# Tacho_Update_Platine_mehrfach.net
KiCad netlist of a schematic drawn in EAGLE
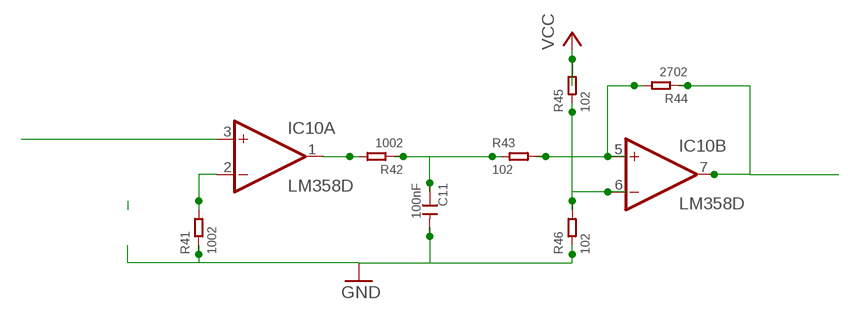
[diagram p0: schematic, sheet 1]
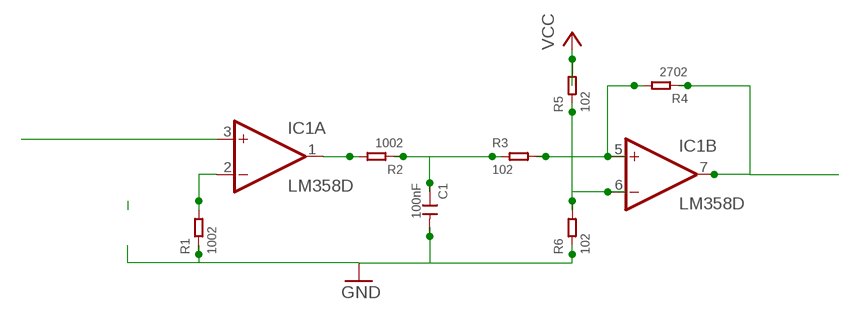
[diagram p1: schematic, sheet 2]
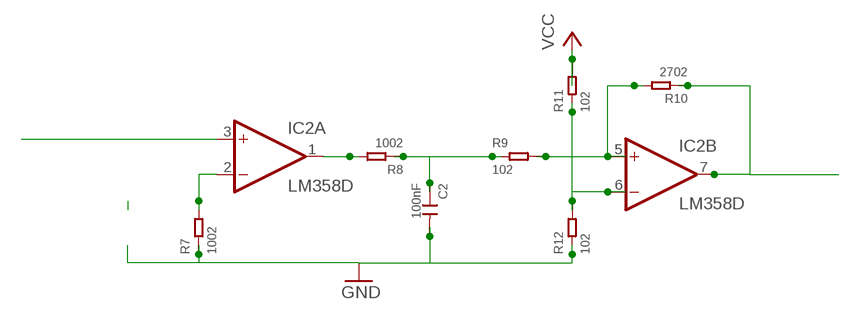
[diagram p2: schematic, sheet 3]
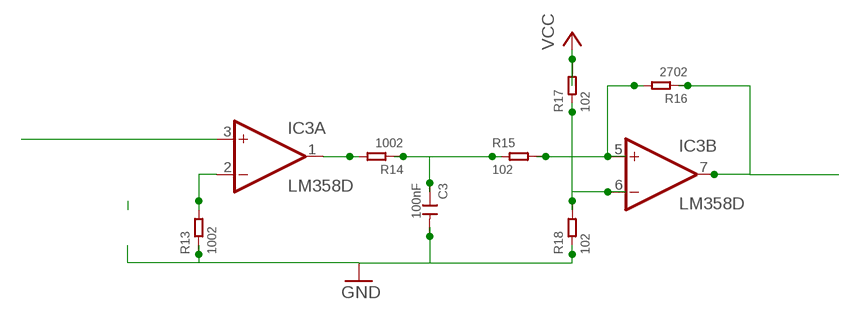
[diagram p3: schematic, sheet 4]
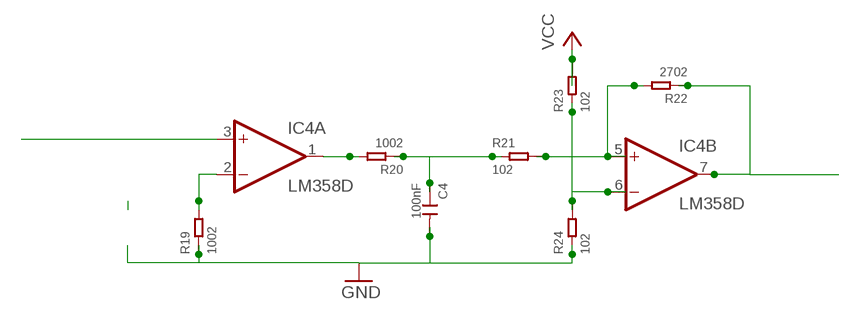
[diagram p4: schematic, sheet 5]
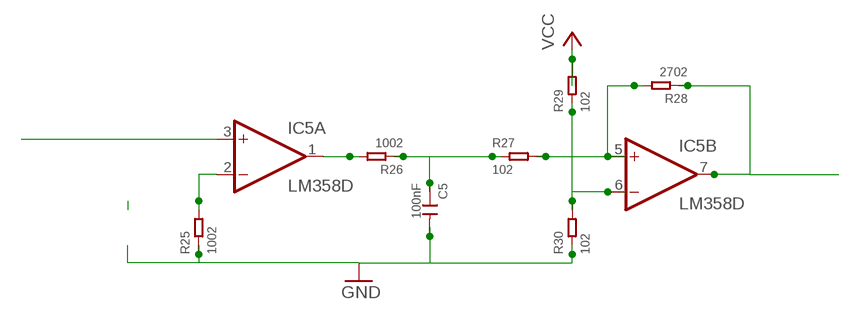
[diagram p5: schematic, sheet 6]
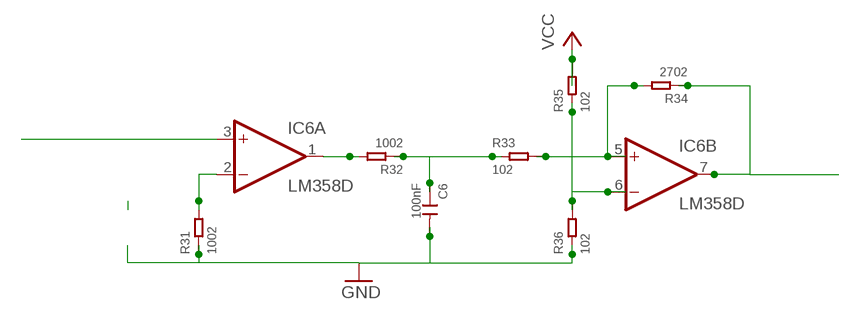
[diagram p6: schematic, sheet 7]
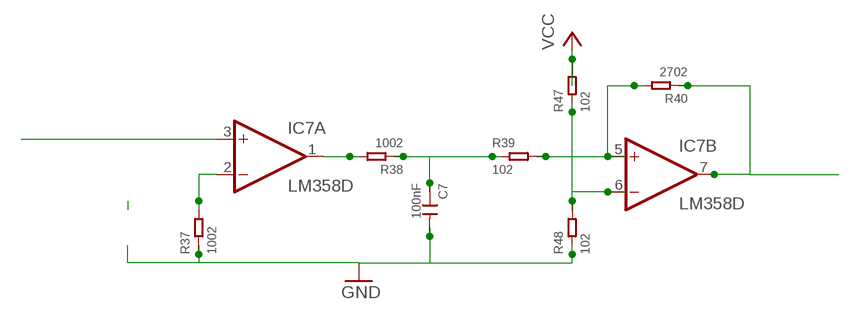
[diagram p7: schematic, sheet 8]
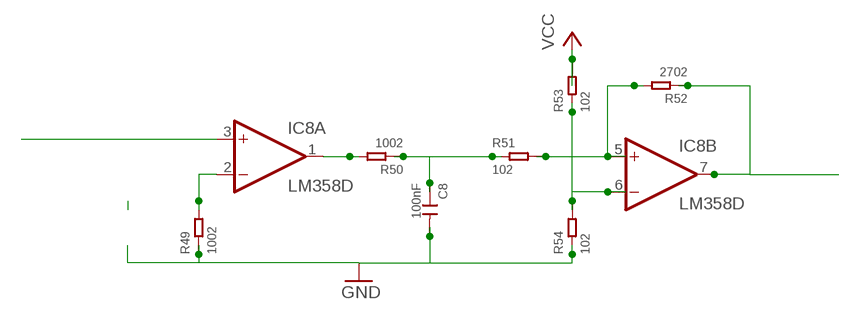
[diagram p8: schematic, sheet 9]
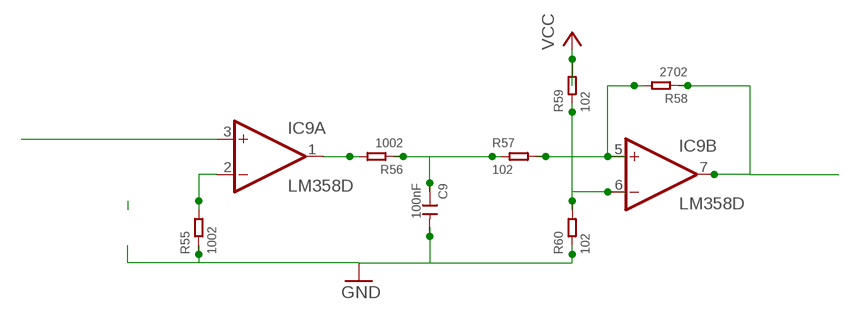
[diagram p9: schematic, sheet 10]
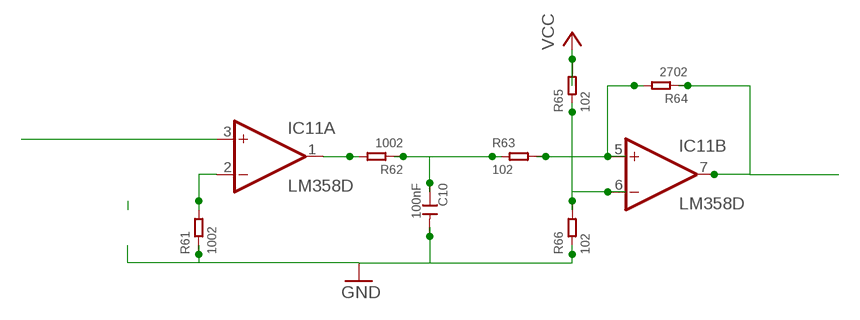
[diagram p10: schematic, sheet 11]
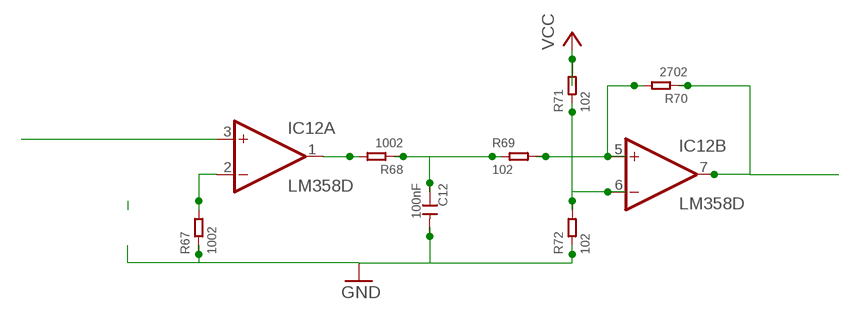
[diagram p11: schematic, sheet 12]
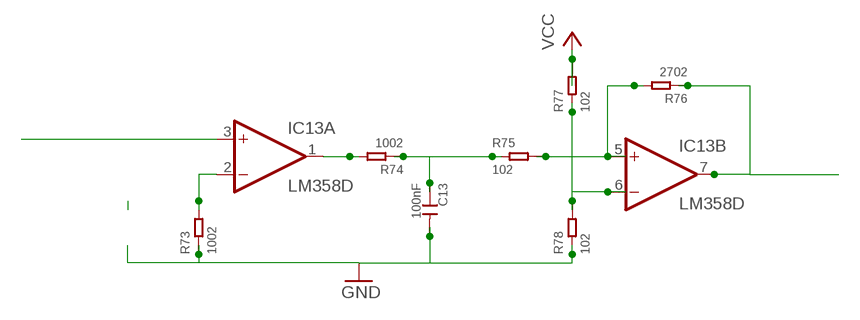
[diagram p12: schematic, sheet 13]
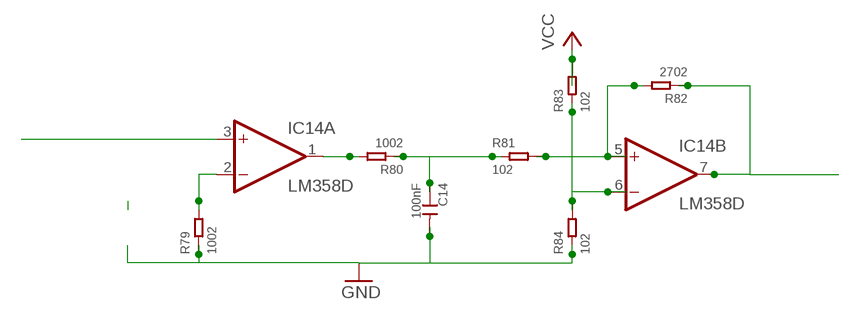
[diagram p13: schematic, sheet 14]
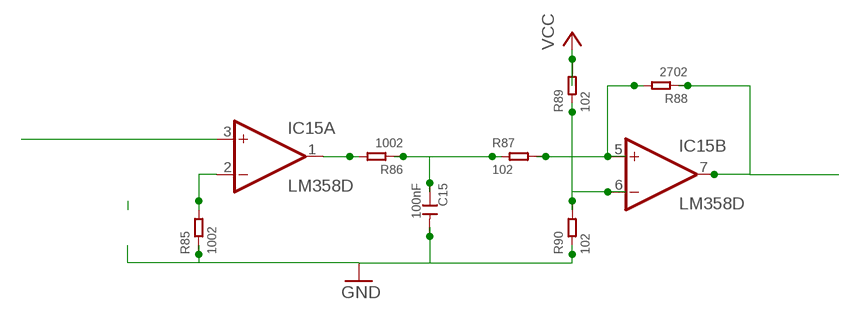
[diagram p14: schematic, sheet 15]
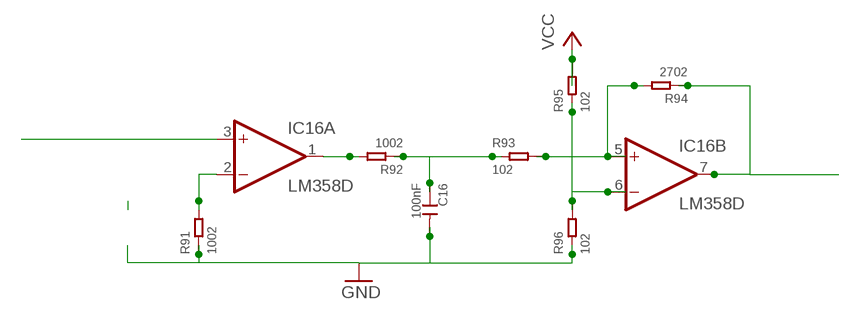
[diagram p15: schematic, sheet 16]

(export (version "E")
  (design (tool "Eeschema 10.0.6"))
  (components
    (comp (ref "C10")
      (value "100nF")
      (footprint "eagle-import:C0805")
      (fields (field (name "MPN") "CC0805KRX7R9BB104"))
      (libsource (lib "eagle-import") (part "CERAMIC-100NF-50V-10%-X7R(0805)"))
    )
    (comp (ref "IC11")
      (value "LM358D")
      (footprint "eagle-import:SO08")
      (libsource (lib "eagle-import") (part "LM358D"))
    )
    (comp (ref "R61")
      (value "1002")
      (footprint "eagle-import:R0805")
      (fields (field (name "MPN") "RC0805FR-0710KL"))
      (libsource (lib "eagle-import") (part "SMD-RES-10K-1%-1/8W(0805)"))
    )
    (comp (ref "R62")
      (value "1002")
      (footprint "eagle-import:R0805")
      (fields (field (name "MPN") "RC0805FR-0710KL"))
      (libsource (lib "eagle-import") (part "SMD-RES-10K-1%-1/8W(0805)"))
    )
    (comp (ref "R63")
      (value "102")
      (footprint "eagle-import:R0805")
      (fields (field (name "MPN") "RC0805JR-071KL"))
      (libsource (lib "eagle-import") (part "SMD-RES-1K-5%-1/8W(0805)"))
    )
    (comp (ref "R64")
      (value "2702")
      (footprint "eagle-import:R0805")
      (fields (field (name "MPN") "RC0805JR-074K7L"))
      (libsource (lib "eagle-import") (part "SMD-RES-4.7K-5%-1/8W(0805)"))
    )
    (comp (ref "R65")
      (value "102")
      (footprint "eagle-import:R0805")
      (fields (field (name "MPN") "RC0805JR-071KL"))
      (libsource (lib "eagle-import") (part "SMD-RES-1K-5%-1/8W(0805)"))
    )
    (comp (ref "R66")
      (value "102")
      (footprint "eagle-import:R0805")
      (fields (field (name "MPN") "RC0805JR-071KL"))
      (libsource (lib "eagle-import") (part "SMD-RES-1K-5%-1/8W(0805)"))
    )
    (comp (ref "C15")
      (value "100nF")
      (footprint "eagle-import:C0805")
      (fields (field (name "MPN") "CC0805KRX7R9BB104"))
      (libsource (lib "eagle-import") (part "CERAMIC-100NF-50V-10%-X7R(0805)"))
    )
    (comp (ref "IC15")
      (value "LM358D")
      (footprint "eagle-import:SO08")
      (libsource (lib "eagle-import") (part "LM358D"))
    )
    (comp (ref "R85")
      (value "1002")
      (footprint "eagle-import:R0805")
      (fields (field (name "MPN") "RC0805FR-0710KL"))
      (libsource (lib "eagle-import") (part "SMD-RES-10K-1%-1/8W(0805)"))
    )
    (comp (ref "R86")
      (value "1002")
      (footprint "eagle-import:R0805")
      (fields (field (name "MPN") "RC0805FR-0710KL"))
      (libsource (lib "eagle-import") (part "SMD-RES-10K-1%-1/8W(0805)"))
    )
    (comp (ref "R87")
      (value "102")
      (footprint "eagle-import:R0805")
      (fields (field (name "MPN") "RC0805JR-071KL"))
      (libsource (lib "eagle-import") (part "SMD-RES-1K-5%-1/8W(0805)"))
    )
    (comp (ref "R88")
      (value "2702")
      (footprint "eagle-import:R0805")
      (fields (field (name "MPN") "RC0805JR-074K7L"))
      (libsource (lib "eagle-import") (part "SMD-RES-4.7K-5%-1/8W(0805)"))
    )
    (comp (ref "R89")
      (value "102")
      (footprint "eagle-import:R0805")
      (fields (field (name "MPN") "RC0805JR-071KL"))
      (libsource (lib "eagle-import") (part "SMD-RES-1K-5%-1/8W(0805)"))
    )
    (comp (ref "R90")
      (value "102")
      (footprint "eagle-import:R0805")
      (fields (field (name "MPN") "RC0805JR-071KL"))
      (libsource (lib "eagle-import") (part "SMD-RES-1K-5%-1/8W(0805)"))
    )
    (comp (ref "C4")
      (value "100nF")
      (footprint "eagle-import:C0805")
      (fields (field (name "MPN") "CC0805KRX7R9BB104"))
      (libsource (lib "eagle-import") (part "CERAMIC-100NF-50V-10%-X7R(0805)"))
    )
    (comp (ref "IC4")
      (value "LM358D")
      (footprint "eagle-import:SO08")
      (libsource (lib "eagle-import") (part "LM358D"))
    )
    (comp (ref "R19")
      (value "1002")
      (footprint "eagle-import:R0805")
      (fields (field (name "MPN") "RC0805FR-0710KL"))
      (libsource (lib "eagle-import") (part "SMD-RES-10K-1%-1/8W(0805)"))
    )
    (comp (ref "R20")
      (value "1002")
      (footprint "eagle-import:R0805")
      (fields (field (name "MPN") "RC0805FR-0710KL"))
      (libsource (lib "eagle-import") (part "SMD-RES-10K-1%-1/8W(0805)"))
    )
    (comp (ref "R21")
      (value "102")
      (footprint "eagle-import:R0805")
      (fields (field (name "MPN") "RC0805JR-071KL"))
      (libsource (lib "eagle-import") (part "SMD-RES-1K-5%-1/8W(0805)"))
    )
    (comp (ref "R22")
      (value "2702")
      (footprint "eagle-import:R0805")
      (fields (field (name "MPN") "RC0805JR-074K7L"))
      (libsource (lib "eagle-import") (part "SMD-RES-4.7K-5%-1/8W(0805)"))
    )
    (comp (ref "R23")
      (value "102")
      (footprint "eagle-import:R0805")
      (fields (field (name "MPN") "RC0805JR-071KL"))
      (libsource (lib "eagle-import") (part "SMD-RES-1K-5%-1/8W(0805)"))
    )
    (comp (ref "R24")
      (value "102")
      (footprint "eagle-import:R0805")
      (fields (field (name "MPN") "RC0805JR-071KL"))
      (libsource (lib "eagle-import") (part "SMD-RES-1K-5%-1/8W(0805)"))
    )
    (comp (ref "C12")
      (value "100nF")
      (footprint "eagle-import:C0805")
      (fields (field (name "MPN") "CC0805KRX7R9BB104"))
      (libsource (lib "eagle-import") (part "CERAMIC-100NF-50V-10%-X7R(0805)"))
    )
    (comp (ref "IC12")
      (value "LM358D")
      (footprint "eagle-import:SO08")
      (libsource (lib "eagle-import") (part "LM358D"))
    )
    (comp (ref "R67")
      (value "1002")
      (footprint "eagle-import:R0805")
      (fields (field (name "MPN") "RC0805FR-0710KL"))
      (libsource (lib "eagle-import") (part "SMD-RES-10K-1%-1/8W(0805)"))
    )
    (comp (ref "R68")
      (value "1002")
      (footprint "eagle-import:R0805")
      (fields (field (name "MPN") "RC0805FR-0710KL"))
      (libsource (lib "eagle-import") (part "SMD-RES-10K-1%-1/8W(0805)"))
    )
    (comp (ref "R69")
      (value "102")
      (footprint "eagle-import:R0805")
      (fields (field (name "MPN") "RC0805JR-071KL"))
      (libsource (lib "eagle-import") (part "SMD-RES-1K-5%-1/8W(0805)"))
    )
    (comp (ref "R70")
      (value "2702")
      (footprint "eagle-import:R0805")
      (fields (field (name "MPN") "RC0805JR-074K7L"))
      (libsource (lib "eagle-import") (part "SMD-RES-4.7K-5%-1/8W(0805)"))
    )
    (comp (ref "R71")
      (value "102")
      (footprint "eagle-import:R0805")
      (fields (field (name "MPN") "RC0805JR-071KL"))
      (libsource (lib "eagle-import") (part "SMD-RES-1K-5%-1/8W(0805)"))
    )
    (comp (ref "R72")
      (value "102")
      (footprint "eagle-import:R0805")
      (fields (field (name "MPN") "RC0805JR-071KL"))
      (libsource (lib "eagle-import") (part "SMD-RES-1K-5%-1/8W(0805)"))
    )
    (comp (ref "C1")
      (value "100nF")
      (footprint "eagle-import:C0805")
      (fields (field (name "MPN") "CC0805KRX7R9BB104"))
      (libsource (lib "eagle-import") (part "CERAMIC-100NF-50V-10%-X7R(0805)"))
    )
    (comp (ref "IC1")
      (value "LM358D")
      (footprint "eagle-import:SO08")
      (libsource (lib "eagle-import") (part "LM358D"))
    )
    (comp (ref "R1")
      (value "1002")
      (footprint "eagle-import:R0805")
      (fields (field (name "MPN") "RC0805FR-0710KL"))
      (libsource (lib "eagle-import") (part "SMD-RES-10K-1%-1/8W(0805)"))
    )
    (comp (ref "R2")
      (value "1002")
      (footprint "eagle-import:R0805")
      (fields (field (name "MPN") "RC0805FR-0710KL"))
      (libsource (lib "eagle-import") (part "SMD-RES-10K-1%-1/8W(0805)"))
    )
    (comp (ref "R3")
      (value "102")
      (footprint "eagle-import:R0805")
      (fields (field (name "MPN") "RC0805JR-071KL"))
      (libsource (lib "eagle-import") (part "SMD-RES-1K-5%-1/8W(0805)"))
    )
    (comp (ref "R4")
      (value "2702")
      (footprint "eagle-import:R0805")
      (fields (field (name "MPN") "RC0805JR-074K7L"))
      (libsource (lib "eagle-import") (part "SMD-RES-4.7K-5%-1/8W(0805)"))
    )
    (comp (ref "R5")
      (value "102")
      (footprint "eagle-import:R0805")
      (fields (field (name "MPN") "RC0805JR-071KL"))
      (libsource (lib "eagle-import") (part "SMD-RES-1K-5%-1/8W(0805)"))
    )
    (comp (ref "R6")
      (value "102")
      (footprint "eagle-import:R0805")
      (fields (field (name "MPN") "RC0805JR-071KL"))
      (libsource (lib "eagle-import") (part "SMD-RES-1K-5%-1/8W(0805)"))
    )
    (comp (ref "C2")
      (value "100nF")
      (footprint "eagle-import:C0805")
      (fields (field (name "MPN") "CC0805KRX7R9BB104"))
      (libsource (lib "eagle-import") (part "CERAMIC-100NF-50V-10%-X7R(0805)"))
    )
    (comp (ref "IC2")
      (value "LM358D")
      (footprint "eagle-import:SO08")
      (libsource (lib "eagle-import") (part "LM358D"))
    )
    (comp (ref "R7")
      (value "1002")
      (footprint "eagle-import:R0805")
      (fields (field (name "MPN") "RC0805FR-0710KL"))
      (libsource (lib "eagle-import") (part "SMD-RES-10K-1%-1/8W(0805)"))
    )
    (comp (ref "R8")
      (value "1002")
      (footprint "eagle-import:R0805")
      (fields (field (name "MPN") "RC0805FR-0710KL"))
      (libsource (lib "eagle-import") (part "SMD-RES-10K-1%-1/8W(0805)"))
    )
    (comp (ref "R9")
      (value "102")
      (footprint "eagle-import:R0805")
      (fields (field (name "MPN") "RC0805JR-071KL"))
      (libsource (lib "eagle-import") (part "SMD-RES-1K-5%-1/8W(0805)"))
    )
    (comp (ref "R10")
      (value "2702")
      (footprint "eagle-import:R0805")
      (fields (field (name "MPN") "RC0805JR-074K7L"))
      (libsource (lib "eagle-import") (part "SMD-RES-4.7K-5%-1/8W(0805)"))
    )
    (comp (ref "R11")
      (value "102")
      (footprint "eagle-import:R0805")
      (fields (field (name "MPN") "RC0805JR-071KL"))
      (libsource (lib "eagle-import") (part "SMD-RES-1K-5%-1/8W(0805)"))
    )
    (comp (ref "R12")
      (value "102")
      (footprint "eagle-import:R0805")
      (fields (field (name "MPN") "RC0805JR-071KL"))
      (libsource (lib "eagle-import") (part "SMD-RES-1K-5%-1/8W(0805)"))
    )
    (comp (ref "C11")
      (value "100nF")
      (footprint "eagle-import:C0805")
      (fields (field (name "MPN") "CC0805KRX7R9BB104"))
      (libsource (lib "eagle-import") (part "CERAMIC-100NF-50V-10%-X7R(0805)"))
    )
    (comp (ref "IC10")
      (value "LM358D")
      (footprint "eagle-import:SO08")
      (libsource (lib "eagle-import") (part "LM358D"))
    )
    (comp (ref "R41")
      (value "1002")
      (footprint "eagle-import:R0805")
      (fields (field (name "MPN") "RC0805FR-0710KL"))
      (libsource (lib "eagle-import") (part "SMD-RES-10K-1%-1/8W(0805)"))
    )
    (comp (ref "R42")
      (value "1002")
      (footprint "eagle-import:R0805")
      (fields (field (name "MPN") "RC0805FR-0710KL"))
      (libsource (lib "eagle-import") (part "SMD-RES-10K-1%-1/8W(0805)"))
    )
    (comp (ref "R43")
      (value "102")
      (footprint "eagle-import:R0805")
      (fields (field (name "MPN") "RC0805JR-071KL"))
      (libsource (lib "eagle-import") (part "SMD-RES-1K-5%-1/8W(0805)"))
    )
    (comp (ref "R44")
      (value "2702")
      (footprint "eagle-import:R0805")
      (fields (field (name "MPN") "RC0805JR-074K7L"))
      (libsource (lib "eagle-import") (part "SMD-RES-4.7K-5%-1/8W(0805)"))
    )
    (comp (ref "R45")
      (value "102")
      (footprint "eagle-import:R0805")
      (fields (field (name "MPN") "RC0805JR-071KL"))
      (libsource (lib "eagle-import") (part "SMD-RES-1K-5%-1/8W(0805)"))
    )
    (comp (ref "R46")
      (value "102")
      (footprint "eagle-import:R0805")
      (fields (field (name "MPN") "RC0805JR-071KL"))
      (libsource (lib "eagle-import") (part "SMD-RES-1K-5%-1/8W(0805)"))
    )
    (comp (ref "C13")
      (value "100nF")
      (footprint "eagle-import:C0805")
      (fields (field (name "MPN") "CC0805KRX7R9BB104"))
      (libsource (lib "eagle-import") (part "CERAMIC-100NF-50V-10%-X7R(0805)"))
    )
    (comp (ref "IC13")
      (value "LM358D")
      (footprint "eagle-import:SO08")
      (libsource (lib "eagle-import") (part "LM358D"))
    )
    (comp (ref "R73")
      (value "1002")
      (footprint "eagle-import:R0805")
      (fields (field (name "MPN") "RC0805FR-0710KL"))
      (libsource (lib "eagle-import") (part "SMD-RES-10K-1%-1/8W(0805)"))
    )
    (comp (ref "R74")
      (value "1002")
      (footprint "eagle-import:R0805")
      (fields (field (name "MPN") "RC0805FR-0710KL"))
      (libsource (lib "eagle-import") (part "SMD-RES-10K-1%-1/8W(0805)"))
    )
    (comp (ref "R75")
      (value "102")
      (footprint "eagle-import:R0805")
      (fields (field (name "MPN") "RC0805JR-071KL"))
      (libsource (lib "eagle-import") (part "SMD-RES-1K-5%-1/8W(0805)"))
    )
    (comp (ref "R76")
      (value "2702")
      (footprint "eagle-import:R0805")
      (fields (field (name "MPN") "RC0805JR-074K7L"))
      (libsource (lib "eagle-import") (part "SMD-RES-4.7K-5%-1/8W(0805)"))
    )
    (comp (ref "R77")
      (value "102")
      (footprint "eagle-import:R0805")
      (fields (field (name "MPN") "RC0805JR-071KL"))
      (libsource (lib "eagle-import") (part "SMD-RES-1K-5%-1/8W(0805)"))
    )
    (comp (ref "R78")
      (value "102")
      (footprint "eagle-import:R0805")
      (fields (field (name "MPN") "RC0805JR-071KL"))
      (libsource (lib "eagle-import") (part "SMD-RES-1K-5%-1/8W(0805)"))
    )
    (comp (ref "C9")
      (value "100nF")
      (footprint "eagle-import:C0805")
      (fields (field (name "MPN") "CC0805KRX7R9BB104"))
      (libsource (lib "eagle-import") (part "CERAMIC-100NF-50V-10%-X7R(0805)"))
    )
    (comp (ref "IC9")
      (value "LM358D")
      (footprint "eagle-import:SO08")
      (libsource (lib "eagle-import") (part "LM358D"))
    )
    (comp (ref "R55")
      (value "1002")
      (footprint "eagle-import:R0805")
      (fields (field (name "MPN") "RC0805FR-0710KL"))
      (libsource (lib "eagle-import") (part "SMD-RES-10K-1%-1/8W(0805)"))
    )
    (comp (ref "R56")
      (value "1002")
      (footprint "eagle-import:R0805")
      (fields (field (name "MPN") "RC0805FR-0710KL"))
      (libsource (lib "eagle-import") (part "SMD-RES-10K-1%-1/8W(0805)"))
    )
    (comp (ref "R57")
      (value "102")
      (footprint "eagle-import:R0805")
      (fields (field (name "MPN") "RC0805JR-071KL"))
      (libsource (lib "eagle-import") (part "SMD-RES-1K-5%-1/8W(0805)"))
    )
    (comp (ref "R58")
      (value "2702")
      (footprint "eagle-import:R0805")
      (fields (field (name "MPN") "RC0805JR-074K7L"))
      (libsource (lib "eagle-import") (part "SMD-RES-4.7K-5%-1/8W(0805)"))
    )
    (comp (ref "R59")
      (value "102")
      (footprint "eagle-import:R0805")
      (fields (field (name "MPN") "RC0805JR-071KL"))
      (libsource (lib "eagle-import") (part "SMD-RES-1K-5%-1/8W(0805)"))
    )
    (comp (ref "R60")
      (value "102")
      (footprint "eagle-import:R0805")
      (fields (field (name "MPN") "RC0805JR-071KL"))
      (libsource (lib "eagle-import") (part "SMD-RES-1K-5%-1/8W(0805)"))
    )
    (comp (ref "C5")
      (value "100nF")
      (footprint "eagle-import:C0805")
      (fields (field (name "MPN") "CC0805KRX7R9BB104"))
      (libsource (lib "eagle-import") (part "CERAMIC-100NF-50V-10%-X7R(0805)"))
    )
    (comp (ref "IC5")
      (value "LM358D")
      (footprint "eagle-import:SO08")
      (libsource (lib "eagle-import") (part "LM358D"))
    )
    (comp (ref "R25")
      (value "1002")
      (footprint "eagle-import:R0805")
      (fields (field (name "MPN") "RC0805FR-0710KL"))
      (libsource (lib "eagle-import") (part "SMD-RES-10K-1%-1/8W(0805)"))
    )
    (comp (ref "R26")
      (value "1002")
      (footprint "eagle-import:R0805")
      (fields (field (name "MPN") "RC0805FR-0710KL"))
      (libsource (lib "eagle-import") (part "SMD-RES-10K-1%-1/8W(0805)"))
    )
    (comp (ref "R27")
      (value "102")
      (footprint "eagle-import:R0805")
      (fields (field (name "MPN") "RC0805JR-071KL"))
      (libsource (lib "eagle-import") (part "SMD-RES-1K-5%-1/8W(0805)"))
    )
    (comp (ref "R28")
      (value "2702")
      (footprint "eagle-import:R0805")
      (fields (field (name "MPN") "RC0805JR-074K7L"))
      (libsource (lib "eagle-import") (part "SMD-RES-4.7K-5%-1/8W(0805)"))
    )
    (comp (ref "R29")
      (value "102")
      (footprint "eagle-import:R0805")
      (fields (field (name "MPN") "RC0805JR-071KL"))
      (libsource (lib "eagle-import") (part "SMD-RES-1K-5%-1/8W(0805)"))
    )
    (comp (ref "R30")
      (value "102")
      (footprint "eagle-import:R0805")
      (fields (field (name "MPN") "RC0805JR-071KL"))
      (libsource (lib "eagle-import") (part "SMD-RES-1K-5%-1/8W(0805)"))
    )
    (comp (ref "C16")
      (value "100nF")
      (footprint "eagle-import:C0805")
      (fields (field (name "MPN") "CC0805KRX7R9BB104"))
      (libsource (lib "eagle-import") (part "CERAMIC-100NF-50V-10%-X7R(0805)"))
    )
    (comp (ref "IC16")
      (value "LM358D")
      (footprint "eagle-import:SO08")
      (libsource (lib "eagle-import") (part "LM358D"))
    )
    (comp (ref "R91")
      (value "1002")
      (footprint "eagle-import:R0805")
      (fields (field (name "MPN") "RC0805FR-0710KL"))
      (libsource (lib "eagle-import") (part "SMD-RES-10K-1%-1/8W(0805)"))
    )
    (comp (ref "R92")
      (value "1002")
      (footprint "eagle-import:R0805")
      (fields (field (name "MPN") "RC0805FR-0710KL"))
      (libsource (lib "eagle-import") (part "SMD-RES-10K-1%-1/8W(0805)"))
    )
    (comp (ref "R93")
      (value "102")
      (footprint "eagle-import:R0805")
      (fields (field (name "MPN") "RC0805JR-071KL"))
      (libsource (lib "eagle-import") (part "SMD-RES-1K-5%-1/8W(0805)"))
    )
    (comp (ref "R94")
      (value "2702")
      (footprint "eagle-import:R0805")
      (fields (field (name "MPN") "RC0805JR-074K7L"))
      (libsource (lib "eagle-import") (part "SMD-RES-4.7K-5%-1/8W(0805)"))
    )
    (comp (ref "R95")
      (value "102")
      (footprint "eagle-import:R0805")
      (fields (field (name "MPN") "RC0805JR-071KL"))
      (libsource (lib "eagle-import") (part "SMD-RES-1K-5%-1/8W(0805)"))
    )
    (comp (ref "R96")
      (value "102")
      (footprint "eagle-import:R0805")
      (fields (field (name "MPN") "RC0805JR-071KL"))
      (libsource (lib "eagle-import") (part "SMD-RES-1K-5%-1/8W(0805)"))
    )
    (comp (ref "C3")
      (value "100nF")
      (footprint "eagle-import:C0805")
      (fields (field (name "MPN") "CC0805KRX7R9BB104"))
      (libsource (lib "eagle-import") (part "CERAMIC-100NF-50V-10%-X7R(0805)"))
    )
    (comp (ref "IC3")
      (value "LM358D")
      (footprint "eagle-import:SO08")
      (libsource (lib "eagle-import") (part "LM358D"))
    )
    (comp (ref "R13")
      (value "1002")
      (footprint "eagle-import:R0805")
      (fields (field (name "MPN") "RC0805FR-0710KL"))
      (libsource (lib "eagle-import") (part "SMD-RES-10K-1%-1/8W(0805)"))
    )
    (comp (ref "R14")
      (value "1002")
      (footprint "eagle-import:R0805")
      (fields (field (name "MPN") "RC0805FR-0710KL"))
      (libsource (lib "eagle-import") (part "SMD-RES-10K-1%-1/8W(0805)"))
    )
    (comp (ref "R15")
      (value "102")
      (footprint "eagle-import:R0805")
      (fields (field (name "MPN") "RC0805JR-071KL"))
      (libsource (lib "eagle-import") (part "SMD-RES-1K-5%-1/8W(0805)"))
    )
    (comp (ref "R16")
      (value "2702")
      (footprint "eagle-import:R0805")
      (fields (field (name "MPN") "RC0805JR-074K7L"))
      (libsource (lib "eagle-import") (part "SMD-RES-4.7K-5%-1/8W(0805)"))
    )
    (comp (ref "R17")
      (value "102")
      (footprint "eagle-import:R0805")
      (fields (field (name "MPN") "RC0805JR-071KL"))
      (libsource (lib "eagle-import") (part "SMD-RES-1K-5%-1/8W(0805)"))
    )
    (comp (ref "R18")
      (value "102")
      (footprint "eagle-import:R0805")
      (fields (field (name "MPN") "RC0805JR-071KL"))
      (libsource (lib "eagle-import") (part "SMD-RES-1K-5%-1/8W(0805)"))
    )
    (comp (ref "C14")
      (value "100nF")
      (footprint "eagle-import:C0805")
      (fields (field (name "MPN") "CC0805KRX7R9BB104"))
      (libsource (lib "eagle-import") (part "CERAMIC-100NF-50V-10%-X7R(0805)"))
    )
    (comp (ref "IC14")
      (value "LM358D")
      (footprint "eagle-import:SO08")
      (libsource (lib "eagle-import") (part "LM358D"))
    )
    (comp (ref "R79")
      (value "1002")
      (footprint "eagle-import:R0805")
      (fields (field (name "MPN") "RC0805FR-0710KL"))
      (libsource (lib "eagle-import") (part "SMD-RES-10K-1%-1/8W(0805)"))
    )
    (comp (ref "R80")
      (value "1002")
      (footprint "eagle-import:R0805")
      (fields (field (name "MPN") "RC0805FR-0710KL"))
      (libsource (lib "eagle-import") (part "SMD-RES-10K-1%-1/8W(0805)"))
    )
    (comp (ref "R81")
      (value "102")
      (footprint "eagle-import:R0805")
      (fields (field (name "MPN") "RC0805JR-071KL"))
      (libsource (lib "eagle-import") (part "SMD-RES-1K-5%-1/8W(0805)"))
    )
    (comp (ref "R82")
      (value "2702")
      (footprint "eagle-import:R0805")
      (fields (field (name "MPN") "RC0805JR-074K7L"))
      (libsource (lib "eagle-import") (part "SMD-RES-4.7K-5%-1/8W(0805)"))
    )
    (comp (ref "R83")
      (value "102")
      (footprint "eagle-import:R0805")
      (fields (field (name "MPN") "RC0805JR-071KL"))
      (libsource (lib "eagle-import") (part "SMD-RES-1K-5%-1/8W(0805)"))
    )
    (comp (ref "R84")
      (value "102")
      (footprint "eagle-import:R0805")
      (fields (field (name "MPN") "RC0805JR-071KL"))
      (libsource (lib "eagle-import") (part "SMD-RES-1K-5%-1/8W(0805)"))
    )
    (comp (ref "C7")
      (value "100nF")
      (footprint "eagle-import:C0805")
      (fields (field (name "MPN") "CC0805KRX7R9BB104"))
      (libsource (lib "eagle-import") (part "CERAMIC-100NF-50V-10%-X7R(0805)"))
    )
    (comp (ref "IC7")
      (value "LM358D")
      (footprint "eagle-import:SO08")
      (libsource (lib "eagle-import") (part "LM358D"))
    )
    (comp (ref "R37")
      (value "1002")
      (footprint "eagle-import:R0805")
      (fields (field (name "MPN") "RC0805FR-0710KL"))
      (libsource (lib "eagle-import") (part "SMD-RES-10K-1%-1/8W(0805)"))
    )
    (comp (ref "R38")
      (value "1002")
      (footprint "eagle-import:R0805")
      (fields (field (name "MPN") "RC0805FR-0710KL"))
      (libsource (lib "eagle-import") (part "SMD-RES-10K-1%-1/8W(0805)"))
    )
    (comp (ref "R39")
      (value "102")
      (footprint "eagle-import:R0805")
      (fields (field (name "MPN") "RC0805JR-071KL"))
      (libsource (lib "eagle-import") (part "SMD-RES-1K-5%-1/8W(0805)"))
    )
    (comp (ref "R40")
      (value "2702")
      (footprint "eagle-import:R0805")
      (fields (field (name "MPN") "RC0805JR-074K7L"))
      (libsource (lib "eagle-import") (part "SMD-RES-4.7K-5%-1/8W(0805)"))
    )
    (comp (ref "R47")
      (value "102")
      (footprint "eagle-import:R0805")
      (fields (field (name "MPN") "RC0805JR-071KL"))
      (libsource (lib "eagle-import") (part "SMD-RES-1K-5%-1/8W(0805)"))
    )
    (comp (ref "R48")
      (value "102")
      (footprint "eagle-import:R0805")
      (fields (field (name "MPN") "RC0805JR-071KL"))
      (libsource (lib "eagle-import") (part "SMD-RES-1K-5%-1/8W(0805)"))
    )
    (comp (ref "C8")
      (value "100nF")
      (footprint "eagle-import:C0805")
      (fields (field (name "MPN") "CC0805KRX7R9BB104"))
      (libsource (lib "eagle-import") (part "CERAMIC-100NF-50V-10%-X7R(0805)"))
    )
    (comp (ref "IC8")
      (value "LM358D")
      (footprint "eagle-import:SO08")
      (libsource (lib "eagle-import") (part "LM358D"))
    )
    (comp (ref "R49")
      (value "1002")
      (footprint "eagle-import:R0805")
      (fields (field (name "MPN") "RC0805FR-0710KL"))
      (libsource (lib "eagle-import") (part "SMD-RES-10K-1%-1/8W(0805)"))
    )
    (comp (ref "R50")
      (value "1002")
      (footprint "eagle-import:R0805")
      (fields (field (name "MPN") "RC0805FR-0710KL"))
      (libsource (lib "eagle-import") (part "SMD-RES-10K-1%-1/8W(0805)"))
    )
    (comp (ref "R51")
      (value "102")
      (footprint "eagle-import:R0805")
      (fields (field (name "MPN") "RC0805JR-071KL"))
      (libsource (lib "eagle-import") (part "SMD-RES-1K-5%-1/8W(0805)"))
    )
    (comp (ref "R52")
      (value "2702")
      (footprint "eagle-import:R0805")
      (fields (field (name "MPN") "RC0805JR-074K7L"))
      (libsource (lib "eagle-import") (part "SMD-RES-4.7K-5%-1/8W(0805)"))
    )
    (comp (ref "R53")
      (value "102")
      (footprint "eagle-import:R0805")
      (fields (field (name "MPN") "RC0805JR-071KL"))
      (libsource (lib "eagle-import") (part "SMD-RES-1K-5%-1/8W(0805)"))
    )
    (comp (ref "R54")
      (value "102")
      (footprint "eagle-import:R0805")
      (fields (field (name "MPN") "RC0805JR-071KL"))
      (libsource (lib "eagle-import") (part "SMD-RES-1K-5%-1/8W(0805)"))
    )
    (comp (ref "C6")
      (value "100nF")
      (footprint "eagle-import:C0805")
      (fields (field (name "MPN") "CC0805KRX7R9BB104"))
      (libsource (lib "eagle-import") (part "CERAMIC-100NF-50V-10%-X7R(0805)"))
    )
    (comp (ref "IC6")
      (value "LM358D")
      (footprint "eagle-import:SO08")
      (libsource (lib "eagle-import") (part "LM358D"))
    )
    (comp (ref "R31")
      (value "1002")
      (footprint "eagle-import:R0805")
      (fields (field (name "MPN") "RC0805FR-0710KL"))
      (libsource (lib "eagle-import") (part "SMD-RES-10K-1%-1/8W(0805)"))
    )
    (comp (ref "R32")
      (value "1002")
      (footprint "eagle-import:R0805")
      (fields (field (name "MPN") "RC0805FR-0710KL"))
      (libsource (lib "eagle-import") (part "SMD-RES-10K-1%-1/8W(0805)"))
    )
    (comp (ref "R33")
      (value "102")
      (footprint "eagle-import:R0805")
      (fields (field (name "MPN") "RC0805JR-071KL"))
      (libsource (lib "eagle-import") (part "SMD-RES-1K-5%-1/8W(0805)"))
    )
    (comp (ref "R34")
      (value "2702")
      (footprint "eagle-import:R0805")
      (fields (field (name "MPN") "RC0805JR-074K7L"))
      (libsource (lib "eagle-import") (part "SMD-RES-4.7K-5%-1/8W(0805)"))
    )
    (comp (ref "R35")
      (value "102")
      (footprint "eagle-import:R0805")
      (fields (field (name "MPN") "RC0805JR-071KL"))
      (libsource (lib "eagle-import") (part "SMD-RES-1K-5%-1/8W(0805)"))
    )
    (comp (ref "R36")
      (value "102")
      (footprint "eagle-import:R0805")
      (fields (field (name "MPN") "RC0805JR-071KL"))
      (libsource (lib "eagle-import") (part "SMD-RES-1K-5%-1/8W(0805)"))
    )
  )
  (nets
    (net (code "1") (name "GND") (class "Default")
      (node (ref "C1") (pin "2") (pinfunction "2_2") (pintype "passive"))
      (node (ref "C10") (pin "2") (pinfunction "2_2") (pintype "passive"))
      (node (ref "C11") (pin "2") (pinfunction "2_2") (pintype "passive"))
      (node (ref "C12") (pin "2") (pinfunction "2_2") (pintype "passive"))
      (node (ref "C13") (pin "2") (pinfunction "2_2") (pintype "passive"))
      (node (ref "C14") (pin "2") (pinfunction "2_2") (pintype "passive"))
      (node (ref "C15") (pin "2") (pinfunction "2_2") (pintype "passive"))
      (node (ref "C16") (pin "2") (pinfunction "2_2") (pintype "passive"))
      (node (ref "C2") (pin "2") (pinfunction "2_2") (pintype "passive"))
      (node (ref "C3") (pin "2") (pinfunction "2_2") (pintype "passive"))
      (node (ref "C4") (pin "2") (pinfunction "2_2") (pintype "passive"))
      (node (ref "C5") (pin "2") (pinfunction "2_2") (pintype "passive"))
      (node (ref "C6") (pin "2") (pinfunction "2_2") (pintype "passive"))
      (node (ref "C7") (pin "2") (pinfunction "2_2") (pintype "passive"))
      (node (ref "C8") (pin "2") (pinfunction "2_2") (pintype "passive"))
      (node (ref "C9") (pin "2") (pinfunction "2_2") (pintype "passive"))
      (node (ref "R1") (pin "1") (pinfunction "1_1") (pintype "passive"))
      (node (ref "R12") (pin "1") (pinfunction "1_1") (pintype "passive"))
      (node (ref "R13") (pin "1") (pinfunction "1_1") (pintype "passive"))
      (node (ref "R18") (pin "1") (pinfunction "1_1") (pintype "passive"))
      (node (ref "R19") (pin "1") (pinfunction "1_1") (pintype "passive"))
      (node (ref "R24") (pin "1") (pinfunction "1_1") (pintype "passive"))
      (node (ref "R25") (pin "1") (pinfunction "1_1") (pintype "passive"))
      (node (ref "R30") (pin "1") (pinfunction "1_1") (pintype "passive"))
      (node (ref "R31") (pin "1") (pinfunction "1_1") (pintype "passive"))
      (node (ref "R36") (pin "1") (pinfunction "1_1") (pintype "passive"))
      (node (ref "R37") (pin "1") (pinfunction "1_1") (pintype "passive"))
      (node (ref "R41") (pin "1") (pinfunction "1_1") (pintype "passive"))
      (node (ref "R46") (pin "1") (pinfunction "1_1") (pintype "passive"))
      (node (ref "R48") (pin "1") (pinfunction "1_1") (pintype "passive"))
      (node (ref "R49") (pin "1") (pinfunction "1_1") (pintype "passive"))
      (node (ref "R54") (pin "1") (pinfunction "1_1") (pintype "passive"))
      (node (ref "R55") (pin "1") (pinfunction "1_1") (pintype "passive"))
      (node (ref "R6") (pin "1") (pinfunction "1_1") (pintype "passive"))
      (node (ref "R60") (pin "1") (pinfunction "1_1") (pintype "passive"))
      (node (ref "R61") (pin "1") (pinfunction "1_1") (pintype "passive"))
      (node (ref "R66") (pin "1") (pinfunction "1_1") (pintype "passive"))
      (node (ref "R67") (pin "1") (pinfunction "1_1") (pintype "passive"))
      (node (ref "R7") (pin "1") (pinfunction "1_1") (pintype "passive"))
      (node (ref "R72") (pin "1") (pinfunction "1_1") (pintype "passive"))
      (node (ref "R73") (pin "1") (pinfunction "1_1") (pintype "passive"))
      (node (ref "R78") (pin "1") (pinfunction "1_1") (pintype "passive"))
      (node (ref "R79") (pin "1") (pinfunction "1_1") (pintype "passive"))
      (node (ref "R84") (pin "1") (pinfunction "1_1") (pintype "passive"))
      (node (ref "R85") (pin "1") (pinfunction "1_1") (pintype "passive"))
      (node (ref "R90") (pin "1") (pinfunction "1_1") (pintype "passive"))
      (node (ref "R91") (pin "1") (pinfunction "1_1") (pintype "passive"))
      (node (ref "R96") (pin "1") (pinfunction "1_1") (pintype "passive"))
    )
    (net (code "2") (name "Net-(C1-Pad1)") (class "Default")
      (node (ref "C1") (pin "1") (pinfunction "1_1") (pintype "passive"))
      (node (ref "R2") (pin "1") (pinfunction "1_1") (pintype "passive"))
      (node (ref "R3") (pin "1") (pinfunction "1_1") (pintype "passive"))
    )
    (net (code "3") (name "Net-(C2-Pad1)") (class "Default")
      (node (ref "C2") (pin "1") (pinfunction "1_1") (pintype "passive"))
      (node (ref "R8") (pin "1") (pinfunction "1_1") (pintype "passive"))
      (node (ref "R9") (pin "1") (pinfunction "1_1") (pintype "passive"))
    )
    (net (code "4") (name "Net-(C3-Pad1)") (class "Default")
      (node (ref "C3") (pin "1") (pinfunction "1_1") (pintype "passive"))
      (node (ref "R14") (pin "1") (pinfunction "1_1") (pintype "passive"))
      (node (ref "R15") (pin "1") (pinfunction "1_1") (pintype "passive"))
    )
    (net (code "5") (name "Net-(C4-Pad1)") (class "Default")
      (node (ref "C4") (pin "1") (pinfunction "1_1") (pintype "passive"))
      (node (ref "R20") (pin "1") (pinfunction "1_1") (pintype "passive"))
      (node (ref "R21") (pin "1") (pinfunction "1_1") (pintype "passive"))
    )
    (net (code "6") (name "Net-(C5-Pad1)") (class "Default")
      (node (ref "C5") (pin "1") (pinfunction "1_1") (pintype "passive"))
      (node (ref "R26") (pin "1") (pinfunction "1_1") (pintype "passive"))
      (node (ref "R27") (pin "1") (pinfunction "1_1") (pintype "passive"))
    )
    (net (code "7") (name "Net-(C6-Pad1)") (class "Default")
      (node (ref "C6") (pin "1") (pinfunction "1_1") (pintype "passive"))
      (node (ref "R32") (pin "1") (pinfunction "1_1") (pintype "passive"))
      (node (ref "R33") (pin "1") (pinfunction "1_1") (pintype "passive"))
    )
    (net (code "8") (name "Net-(C7-Pad1)") (class "Default")
      (node (ref "C7") (pin "1") (pinfunction "1_1") (pintype "passive"))
      (node (ref "R38") (pin "1") (pinfunction "1_1") (pintype "passive"))
      (node (ref "R39") (pin "1") (pinfunction "1_1") (pintype "passive"))
    )
    (net (code "9") (name "Net-(C8-Pad1)") (class "Default")
      (node (ref "C8") (pin "1") (pinfunction "1_1") (pintype "passive"))
      (node (ref "R50") (pin "1") (pinfunction "1_1") (pintype "passive"))
      (node (ref "R51") (pin "1") (pinfunction "1_1") (pintype "passive"))
    )
    (net (code "10") (name "Net-(C9-Pad1)") (class "Default")
      (node (ref "C9") (pin "1") (pinfunction "1_1") (pintype "passive"))
      (node (ref "R56") (pin "1") (pinfunction "1_1") (pintype "passive"))
      (node (ref "R57") (pin "1") (pinfunction "1_1") (pintype "passive"))
    )
    (net (code "11") (name "Net-(C10-Pad1)") (class "Default")
      (node (ref "C10") (pin "1") (pinfunction "1_1") (pintype "passive"))
      (node (ref "R62") (pin "1") (pinfunction "1_1") (pintype "passive"))
      (node (ref "R63") (pin "1") (pinfunction "1_1") (pintype "passive"))
    )
    (net (code "12") (name "Net-(C11-Pad1)") (class "Default")
      (node (ref "C11") (pin "1") (pinfunction "1_1") (pintype "passive"))
      (node (ref "R42") (pin "1") (pinfunction "1_1") (pintype "passive"))
      (node (ref "R43") (pin "1") (pinfunction "1_1") (pintype "passive"))
    )
    (net (code "13") (name "Net-(C12-Pad1)") (class "Default")
      (node (ref "C12") (pin "1") (pinfunction "1_1") (pintype "passive"))
      (node (ref "R68") (pin "1") (pinfunction "1_1") (pintype "passive"))
      (node (ref "R69") (pin "1") (pinfunction "1_1") (pintype "passive"))
    )
    (net (code "14") (name "Net-(C13-Pad1)") (class "Default")
      (node (ref "C13") (pin "1") (pinfunction "1_1") (pintype "passive"))
      (node (ref "R74") (pin "1") (pinfunction "1_1") (pintype "passive"))
      (node (ref "R75") (pin "1") (pinfunction "1_1") (pintype "passive"))
    )
    (net (code "15") (name "Net-(C14-Pad1)") (class "Default")
      (node (ref "C14") (pin "1") (pinfunction "1_1") (pintype "passive"))
      (node (ref "R80") (pin "1") (pinfunction "1_1") (pintype "passive"))
      (node (ref "R81") (pin "1") (pinfunction "1_1") (pintype "passive"))
    )
    (net (code "16") (name "Net-(C15-Pad1)") (class "Default")
      (node (ref "C15") (pin "1") (pinfunction "1_1") (pintype "passive"))
      (node (ref "R86") (pin "1") (pinfunction "1_1") (pintype "passive"))
      (node (ref "R87") (pin "1") (pinfunction "1_1") (pintype "passive"))
    )
    (net (code "17") (name "Net-(C16-Pad1)") (class "Default")
      (node (ref "C16") (pin "1") (pinfunction "1_1") (pintype "passive"))
      (node (ref "R92") (pin "1") (pinfunction "1_1") (pintype "passive"))
      (node (ref "R93") (pin "1") (pinfunction "1_1") (pintype "passive"))
    )
    (net (code "18") (name "Net-(IC1A--IN)") (class "Default")
      (node (ref "IC1") (pin "2") (pinfunction "-IN_2") (pintype "input"))
      (node (ref "R1") (pin "2") (pinfunction "2_2") (pintype "passive"))
    )
    (net (code "19") (name "Net-(IC1A-OUT)") (class "Default")
      (node (ref "IC1") (pin "1") (pinfunction "OUT_1") (pintype "output"))
      (node (ref "R2") (pin "2") (pinfunction "2_2") (pintype "passive"))
    )
    (net (code "20") (name "Net-(IC1B-+IN)") (class "Default")
      (node (ref "IC1") (pin "5") (pinfunction "+IN_5") (pintype "input"))
      (node (ref "R3") (pin "2") (pinfunction "2_2") (pintype "passive"))
      (node (ref "R4") (pin "2") (pinfunction "2_2") (pintype "passive"))
    )
    (net (code "21") (name "Net-(IC1B--IN)") (class "Default")
      (node (ref "IC1") (pin "6") (pinfunction "-IN_6") (pintype "input"))
      (node (ref "R5") (pin "1") (pinfunction "1_1") (pintype "passive"))
      (node (ref "R6") (pin "2") (pinfunction "2_2") (pintype "passive"))
    )
    (net (code "22") (name "Net-(IC1B-OUT)") (class "Default")
      (node (ref "IC1") (pin "7") (pinfunction "OUT_7") (pintype "output"))
      (node (ref "R4") (pin "1") (pinfunction "1_1") (pintype "passive"))
    )
    (net (code "23") (name "Net-(IC2A--IN)") (class "Default")
      (node (ref "IC2") (pin "2") (pinfunction "-IN_2") (pintype "input"))
      (node (ref "R7") (pin "2") (pinfunction "2_2") (pintype "passive"))
    )
    (net (code "24") (name "Net-(IC2A-OUT)") (class "Default")
      (node (ref "IC2") (pin "1") (pinfunction "OUT_1") (pintype "output"))
      (node (ref "R8") (pin "2") (pinfunction "2_2") (pintype "passive"))
    )
    (net (code "25") (name "Net-(IC2B-+IN)") (class "Default")
      (node (ref "IC2") (pin "5") (pinfunction "+IN_5") (pintype "input"))
      (node (ref "R10") (pin "2") (pinfunction "2_2") (pintype "passive"))
      (node (ref "R9") (pin "2") (pinfunction "2_2") (pintype "passive"))
    )
    (net (code "26") (name "Net-(IC2B--IN)") (class "Default")
      (node (ref "IC2") (pin "6") (pinfunction "-IN_6") (pintype "input"))
      (node (ref "R11") (pin "1") (pinfunction "1_1") (pintype "passive"))
      (node (ref "R12") (pin "2") (pinfunction "2_2") (pintype "passive"))
    )
    (net (code "27") (name "Net-(IC2B-OUT)") (class "Default")
      (node (ref "IC2") (pin "7") (pinfunction "OUT_7") (pintype "output"))
      (node (ref "R10") (pin "1") (pinfunction "1_1") (pintype "passive"))
    )
    (net (code "28") (name "Net-(IC3A--IN)") (class "Default")
      (node (ref "IC3") (pin "2") (pinfunction "-IN_2") (pintype "input"))
      (node (ref "R13") (pin "2") (pinfunction "2_2") (pintype "passive"))
    )
    (net (code "29") (name "Net-(IC3A-OUT)") (class "Default")
      (node (ref "IC3") (pin "1") (pinfunction "OUT_1") (pintype "output"))
      (node (ref "R14") (pin "2") (pinfunction "2_2") (pintype "passive"))
    )
    (net (code "30") (name "Net-(IC3B-+IN)") (class "Default")
      (node (ref "IC3") (pin "5") (pinfunction "+IN_5") (pintype "input"))
      (node (ref "R15") (pin "2") (pinfunction "2_2") (pintype "passive"))
      (node (ref "R16") (pin "2") (pinfunction "2_2") (pintype "passive"))
    )
    (net (code "31") (name "Net-(IC3B--IN)") (class "Default")
      (node (ref "IC3") (pin "6") (pinfunction "-IN_6") (pintype "input"))
      (node (ref "R17") (pin "1") (pinfunction "1_1") (pintype "passive"))
      (node (ref "R18") (pin "2") (pinfunction "2_2") (pintype "passive"))
    )
    (net (code "32") (name "Net-(IC3B-OUT)") (class "Default")
      (node (ref "IC3") (pin "7") (pinfunction "OUT_7") (pintype "output"))
      (node (ref "R16") (pin "1") (pinfunction "1_1") (pintype "passive"))
    )
    (net (code "33") (name "Net-(IC4A--IN)") (class "Default")
      (node (ref "IC4") (pin "2") (pinfunction "-IN_2") (pintype "input"))
      (node (ref "R19") (pin "2") (pinfunction "2_2") (pintype "passive"))
    )
    (net (code "34") (name "Net-(IC4A-OUT)") (class "Default")
      (node (ref "IC4") (pin "1") (pinfunction "OUT_1") (pintype "output"))
      (node (ref "R20") (pin "2") (pinfunction "2_2") (pintype "passive"))
    )
    (net (code "35") (name "Net-(IC4B-+IN)") (class "Default")
      (node (ref "IC4") (pin "5") (pinfunction "+IN_5") (pintype "input"))
      (node (ref "R21") (pin "2") (pinfunction "2_2") (pintype "passive"))
      (node (ref "R22") (pin "2") (pinfunction "2_2") (pintype "passive"))
    )
    (net (code "36") (name "Net-(IC4B--IN)") (class "Default")
      (node (ref "IC4") (pin "6") (pinfunction "-IN_6") (pintype "input"))
      (node (ref "R23") (pin "1") (pinfunction "1_1") (pintype "passive"))
      (node (ref "R24") (pin "2") (pinfunction "2_2") (pintype "passive"))
    )
    (net (code "37") (name "Net-(IC4B-OUT)") (class "Default")
      (node (ref "IC4") (pin "7") (pinfunction "OUT_7") (pintype "output"))
      (node (ref "R22") (pin "1") (pinfunction "1_1") (pintype "passive"))
    )
    (net (code "38") (name "Net-(IC5A--IN)") (class "Default")
      (node (ref "IC5") (pin "2") (pinfunction "-IN_2") (pintype "input"))
      (node (ref "R25") (pin "2") (pinfunction "2_2") (pintype "passive"))
    )
    (net (code "39") (name "Net-(IC5A-OUT)") (class "Default")
      (node (ref "IC5") (pin "1") (pinfunction "OUT_1") (pintype "output"))
      (node (ref "R26") (pin "2") (pinfunction "2_2") (pintype "passive"))
    )
    (net (code "40") (name "Net-(IC5B-+IN)") (class "Default")
      (node (ref "IC5") (pin "5") (pinfunction "+IN_5") (pintype "input"))
      (node (ref "R27") (pin "2") (pinfunction "2_2") (pintype "passive"))
      (node (ref "R28") (pin "2") (pinfunction "2_2") (pintype "passive"))
    )
    (net (code "41") (name "Net-(IC5B--IN)") (class "Default")
      (node (ref "IC5") (pin "6") (pinfunction "-IN_6") (pintype "input"))
      (node (ref "R29") (pin "1") (pinfunction "1_1") (pintype "passive"))
      (node (ref "R30") (pin "2") (pinfunction "2_2") (pintype "passive"))
    )
    (net (code "42") (name "Net-(IC5B-OUT)") (class "Default")
      (node (ref "IC5") (pin "7") (pinfunction "OUT_7") (pintype "output"))
      (node (ref "R28") (pin "1") (pinfunction "1_1") (pintype "passive"))
    )
    (net (code "43") (name "Net-(IC6A--IN)") (class "Default")
      (node (ref "IC6") (pin "2") (pinfunction "-IN_2") (pintype "input"))
      (node (ref "R31") (pin "2") (pinfunction "2_2") (pintype "passive"))
    )
    (net (code "44") (name "Net-(IC6A-OUT)") (class "Default")
      (node (ref "IC6") (pin "1") (pinfunction "OUT_1") (pintype "output"))
      (node (ref "R32") (pin "2") (pinfunction "2_2") (pintype "passive"))
    )
    (net (code "45") (name "Net-(IC6B-+IN)") (class "Default")
      (node (ref "IC6") (pin "5") (pinfunction "+IN_5") (pintype "input"))
      (node (ref "R33") (pin "2") (pinfunction "2_2") (pintype "passive"))
      (node (ref "R34") (pin "2") (pinfunction "2_2") (pintype "passive"))
    )
    (net (code "46") (name "Net-(IC6B--IN)") (class "Default")
      (node (ref "IC6") (pin "6") (pinfunction "-IN_6") (pintype "input"))
      (node (ref "R35") (pin "1") (pinfunction "1_1") (pintype "passive"))
      (node (ref "R36") (pin "2") (pinfunction "2_2") (pintype "passive"))
    )
    (net (code "47") (name "Net-(IC6B-OUT)") (class "Default")
      (node (ref "IC6") (pin "7") (pinfunction "OUT_7") (pintype "output"))
      (node (ref "R34") (pin "1") (pinfunction "1_1") (pintype "passive"))
    )
    (net (code "48") (name "Net-(IC7A--IN)") (class "Default")
      (node (ref "IC7") (pin "2") (pinfunction "-IN_2") (pintype "input"))
      (node (ref "R37") (pin "2") (pinfunction "2_2") (pintype "passive"))
    )
    (net (code "49") (name "Net-(IC7A-OUT)") (class "Default")
      (node (ref "IC7") (pin "1") (pinfunction "OUT_1") (pintype "output"))
      (node (ref "R38") (pin "2") (pinfunction "2_2") (pintype "passive"))
    )
    (net (code "50") (name "Net-(IC7B-+IN)") (class "Default")
      (node (ref "IC7") (pin "5") (pinfunction "+IN_5") (pintype "input"))
      (node (ref "R39") (pin "2") (pinfunction "2_2") (pintype "passive"))
      (node (ref "R40") (pin "2") (pinfunction "2_2") (pintype "passive"))
    )
    (net (code "51") (name "Net-(IC7B--IN)") (class "Default")
      (node (ref "IC7") (pin "6") (pinfunction "-IN_6") (pintype "input"))
      (node (ref "R47") (pin "1") (pinfunction "1_1") (pintype "passive"))
      (node (ref "R48") (pin "2") (pinfunction "2_2") (pintype "passive"))
    )
    (net (code "52") (name "Net-(IC7B-OUT)") (class "Default")
      (node (ref "IC7") (pin "7") (pinfunction "OUT_7") (pintype "output"))
      (node (ref "R40") (pin "1") (pinfunction "1_1") (pintype "passive"))
    )
    (net (code "53") (name "Net-(IC8A--IN)") (class "Default")
      (node (ref "IC8") (pin "2") (pinfunction "-IN_2") (pintype "input"))
      (node (ref "R49") (pin "2") (pinfunction "2_2") (pintype "passive"))
    )
    (net (code "54") (name "Net-(IC8A-OUT)") (class "Default")
      (node (ref "IC8") (pin "1") (pinfunction "OUT_1") (pintype "output"))
      (node (ref "R50") (pin "2") (pinfunction "2_2") (pintype "passive"))
    )
    (net (code "55") (name "Net-(IC8B-+IN)") (class "Default")
      (node (ref "IC8") (pin "5") (pinfunction "+IN_5") (pintype "input"))
      (node (ref "R51") (pin "2") (pinfunction "2_2") (pintype "passive"))
      (node (ref "R52") (pin "2") (pinfunction "2_2") (pintype "passive"))
    )
    (net (code "56") (name "Net-(IC8B--IN)") (class "Default")
      (node (ref "IC8") (pin "6") (pinfunction "-IN_6") (pintype "input"))
      (node (ref "R53") (pin "1") (pinfunction "1_1") (pintype "passive"))
      (node (ref "R54") (pin "2") (pinfunction "2_2") (pintype "passive"))
    )
    (net (code "57") (name "Net-(IC8B-OUT)") (class "Default")
      (node (ref "IC8") (pin "7") (pinfunction "OUT_7") (pintype "output"))
      (node (ref "R52") (pin "1") (pinfunction "1_1") (pintype "passive"))
    )
    (net (code "58") (name "Net-(IC9A--IN)") (class "Default")
      (node (ref "IC9") (pin "2") (pinfunction "-IN_2") (pintype "input"))
      (node (ref "R55") (pin "2") (pinfunction "2_2") (pintype "passive"))
    )
    (net (code "59") (name "Net-(IC9A-OUT)") (class "Default")
      (node (ref "IC9") (pin "1") (pinfunction "OUT_1") (pintype "output"))
      (node (ref "R56") (pin "2") (pinfunction "2_2") (pintype "passive"))
    )
    (net (code "60") (name "Net-(IC9B-+IN)") (class "Default")
      (node (ref "IC9") (pin "5") (pinfunction "+IN_5") (pintype "input"))
      (node (ref "R57") (pin "2") (pinfunction "2_2") (pintype "passive"))
      (node (ref "R58") (pin "2") (pinfunction "2_2") (pintype "passive"))
    )
    (net (code "61") (name "Net-(IC9B--IN)") (class "Default")
      (node (ref "IC9") (pin "6") (pinfunction "-IN_6") (pintype "input"))
      (node (ref "R59") (pin "1") (pinfunction "1_1") (pintype "passive"))
      (node (ref "R60") (pin "2") (pinfunction "2_2") (pintype "passive"))
    )
    (net (code "62") (name "Net-(IC9B-OUT)") (class "Default")
      (node (ref "IC9") (pin "7") (pinfunction "OUT_7") (pintype "output"))
      (node (ref "R58") (pin "1") (pinfunction "1_1") (pintype "passive"))
    )
    (net (code "63") (name "Net-(IC10A--IN)") (class "Default")
      (node (ref "IC10") (pin "2") (pinfunction "-IN_2") (pintype "input"))
      (node (ref "R41") (pin "2") (pinfunction "2_2") (pintype "passive"))
    )
    (net (code "64") (name "Net-(IC10A-OUT)") (class "Default")
      (node (ref "IC10") (pin "1") (pinfunction "OUT_1") (pintype "output"))
      (node (ref "R42") (pin "2") (pinfunction "2_2") (pintype "passive"))
    )
    (net (code "65") (name "Net-(IC10B-+IN)") (class "Default")
      (node (ref "IC10") (pin "5") (pinfunction "+IN_5") (pintype "input"))
      (node (ref "R43") (pin "2") (pinfunction "2_2") (pintype "passive"))
      (node (ref "R44") (pin "2") (pinfunction "2_2") (pintype "passive"))
    )
    (net (code "66") (name "Net-(IC10B--IN)") (class "Default")
      (node (ref "IC10") (pin "6") (pinfunction "-IN_6") (pintype "input"))
      (node (ref "R45") (pin "1") (pinfunction "1_1") (pintype "passive"))
      (node (ref "R46") (pin "2") (pinfunction "2_2") (pintype "passive"))
    )
    (net (code "67") (name "Net-(IC10B-OUT)") (class "Default")
      (node (ref "IC10") (pin "7") (pinfunction "OUT_7") (pintype "output"))
      (node (ref "R44") (pin "1") (pinfunction "1_1") (pintype "passive"))
    )
    (net (code "68") (name "Net-(IC11A--IN)") (class "Default")
      (node (ref "IC11") (pin "2") (pinfunction "-IN_2") (pintype "input"))
      (node (ref "R61") (pin "2") (pinfunction "2_2") (pintype "passive"))
    )
    (net (code "69") (name "Net-(IC11A-OUT)") (class "Default")
      (node (ref "IC11") (pin "1") (pinfunction "OUT_1") (pintype "output"))
      (node (ref "R62") (pin "2") (pinfunction "2_2") (pintype "passive"))
    )
    (net (code "70") (name "Net-(IC11B-+IN)") (class "Default")
      (node (ref "IC11") (pin "5") (pinfunction "+IN_5") (pintype "input"))
      (node (ref "R63") (pin "2") (pinfunction "2_2") (pintype "passive"))
      (node (ref "R64") (pin "2") (pinfunction "2_2") (pintype "passive"))
    )
    (net (code "71") (name "Net-(IC11B--IN)") (class "Default")
      (node (ref "IC11") (pin "6") (pinfunction "-IN_6") (pintype "input"))
      (node (ref "R65") (pin "1") (pinfunction "1_1") (pintype "passive"))
      (node (ref "R66") (pin "2") (pinfunction "2_2") (pintype "passive"))
    )
    (net (code "72") (name "Net-(IC11B-OUT)") (class "Default")
      (node (ref "IC11") (pin "7") (pinfunction "OUT_7") (pintype "output"))
      (node (ref "R64") (pin "1") (pinfunction "1_1") (pintype "passive"))
    )
    (net (code "73") (name "Net-(IC12A--IN)") (class "Default")
      (node (ref "IC12") (pin "2") (pinfunction "-IN_2") (pintype "input"))
      (node (ref "R67") (pin "2") (pinfunction "2_2") (pintype "passive"))
    )
    (net (code "74") (name "Net-(IC12A-OUT)") (class "Default")
      (node (ref "IC12") (pin "1") (pinfunction "OUT_1") (pintype "output"))
      (node (ref "R68") (pin "2") (pinfunction "2_2") (pintype "passive"))
    )
    (net (code "75") (name "Net-(IC12B-+IN)") (class "Default")
      (node (ref "IC12") (pin "5") (pinfunction "+IN_5") (pintype "input"))
      (node (ref "R69") (pin "2") (pinfunction "2_2") (pintype "passive"))
      (node (ref "R70") (pin "2") (pinfunction "2_2") (pintype "passive"))
    )
    (net (code "76") (name "Net-(IC12B--IN)") (class "Default")
      (node (ref "IC12") (pin "6") (pinfunction "-IN_6") (pintype "input"))
      (node (ref "R71") (pin "1") (pinfunction "1_1") (pintype "passive"))
      (node (ref "R72") (pin "2") (pinfunction "2_2") (pintype "passive"))
    )
    (net (code "77") (name "Net-(IC12B-OUT)") (class "Default")
      (node (ref "IC12") (pin "7") (pinfunction "OUT_7") (pintype "output"))
      (node (ref "R70") (pin "1") (pinfunction "1_1") (pintype "passive"))
    )
    (net (code "78") (name "Net-(IC13A--IN)") (class "Default")
      (node (ref "IC13") (pin "2") (pinfunction "-IN_2") (pintype "input"))
      (node (ref "R73") (pin "2") (pinfunction "2_2") (pintype "passive"))
    )
    (net (code "79") (name "Net-(IC13A-OUT)") (class "Default")
      (node (ref "IC13") (pin "1") (pinfunction "OUT_1") (pintype "output"))
      (node (ref "R74") (pin "2") (pinfunction "2_2") (pintype "passive"))
    )
    (net (code "80") (name "Net-(IC13B-+IN)") (class "Default")
      (node (ref "IC13") (pin "5") (pinfunction "+IN_5") (pintype "input"))
      (node (ref "R75") (pin "2") (pinfunction "2_2") (pintype "passive"))
      (node (ref "R76") (pin "2") (pinfunction "2_2") (pintype "passive"))
    )
    (net (code "81") (name "Net-(IC13B--IN)") (class "Default")
      (node (ref "IC13") (pin "6") (pinfunction "-IN_6") (pintype "input"))
      (node (ref "R77") (pin "1") (pinfunction "1_1") (pintype "passive"))
      (node (ref "R78") (pin "2") (pinfunction "2_2") (pintype "passive"))
    )
    (net (code "82") (name "Net-(IC13B-OUT)") (class "Default")
      (node (ref "IC13") (pin "7") (pinfunction "OUT_7") (pintype "output"))
      (node (ref "R76") (pin "1") (pinfunction "1_1") (pintype "passive"))
    )
    (net (code "83") (name "Net-(IC14A--IN)") (class "Default")
      (node (ref "IC14") (pin "2") (pinfunction "-IN_2") (pintype "input"))
      (node (ref "R79") (pin "2") (pinfunction "2_2") (pintype "passive"))
    )
    (net (code "84") (name "Net-(IC14A-OUT)") (class "Default")
      (node (ref "IC14") (pin "1") (pinfunction "OUT_1") (pintype "output"))
      (node (ref "R80") (pin "2") (pinfunction "2_2") (pintype "passive"))
    )
    (net (code "85") (name "Net-(IC14B-+IN)") (class "Default")
      (node (ref "IC14") (pin "5") (pinfunction "+IN_5") (pintype "input"))
      (node (ref "R81") (pin "2") (pinfunction "2_2") (pintype "passive"))
      (node (ref "R82") (pin "2") (pinfunction "2_2") (pintype "passive"))
    )
    (net (code "86") (name "Net-(IC14B--IN)") (class "Default")
      (node (ref "IC14") (pin "6") (pinfunction "-IN_6") (pintype "input"))
      (node (ref "R83") (pin "1") (pinfunction "1_1") (pintype "passive"))
      (node (ref "R84") (pin "2") (pinfunction "2_2") (pintype "passive"))
    )
    (net (code "87") (name "Net-(IC14B-OUT)") (class "Default")
      (node (ref "IC14") (pin "7") (pinfunction "OUT_7") (pintype "output"))
      (node (ref "R82") (pin "1") (pinfunction "1_1") (pintype "passive"))
    )
    (net (code "88") (name "Net-(IC15A--IN)") (class "Default")
      (node (ref "IC15") (pin "2") (pinfunction "-IN_2") (pintype "input"))
      (node (ref "R85") (pin "2") (pinfunction "2_2") (pintype "passive"))
    )
    (net (code "89") (name "Net-(IC15A-OUT)") (class "Default")
      (node (ref "IC15") (pin "1") (pinfunction "OUT_1") (pintype "output"))
      (node (ref "R86") (pin "2") (pinfunction "2_2") (pintype "passive"))
    )
    (net (code "90") (name "Net-(IC15B-+IN)") (class "Default")
      (node (ref "IC15") (pin "5") (pinfunction "+IN_5") (pintype "input"))
      (node (ref "R87") (pin "2") (pinfunction "2_2") (pintype "passive"))
      (node (ref "R88") (pin "2") (pinfunction "2_2") (pintype "passive"))
    )
    (net (code "91") (name "Net-(IC15B--IN)") (class "Default")
      (node (ref "IC15") (pin "6") (pinfunction "-IN_6") (pintype "input"))
      (node (ref "R89") (pin "1") (pinfunction "1_1") (pintype "passive"))
      (node (ref "R90") (pin "2") (pinfunction "2_2") (pintype "passive"))
    )
    (net (code "92") (name "Net-(IC15B-OUT)") (class "Default")
      (node (ref "IC15") (pin "7") (pinfunction "OUT_7") (pintype "output"))
      (node (ref "R88") (pin "1") (pinfunction "1_1") (pintype "passive"))
    )
    (net (code "93") (name "Net-(IC16A--IN)") (class "Default")
      (node (ref "IC16") (pin "2") (pinfunction "-IN_2") (pintype "input"))
      (node (ref "R91") (pin "2") (pinfunction "2_2") (pintype "passive"))
    )
    (net (code "94") (name "Net-(IC16A-OUT)") (class "Default")
      (node (ref "IC16") (pin "1") (pinfunction "OUT_1") (pintype "output"))
      (node (ref "R92") (pin "2") (pinfunction "2_2") (pintype "passive"))
    )
    (net (code "95") (name "Net-(IC16B-+IN)") (class "Default")
      (node (ref "IC16") (pin "5") (pinfunction "+IN_5") (pintype "input"))
      (node (ref "R93") (pin "2") (pinfunction "2_2") (pintype "passive"))
      (node (ref "R94") (pin "2") (pinfunction "2_2") (pintype "passive"))
    )
    (net (code "96") (name "Net-(IC16B--IN)") (class "Default")
      (node (ref "IC16") (pin "6") (pinfunction "-IN_6") (pintype "input"))
      (node (ref "R95") (pin "1") (pinfunction "1_1") (pintype "passive"))
      (node (ref "R96") (pin "2") (pinfunction "2_2") (pintype "passive"))
    )
    (net (code "97") (name "Net-(IC16B-OUT)") (class "Default")
      (node (ref "IC16") (pin "7") (pinfunction "OUT_7") (pintype "output"))
      (node (ref "R94") (pin "1") (pinfunction "1_1") (pintype "passive"))
    )
    (net (code "98") (name "VCC") (class "Default")
      (node (ref "R11") (pin "2") (pinfunction "2_2") (pintype "passive"))
      (node (ref "R17") (pin "2") (pinfunction "2_2") (pintype "passive"))
      (node (ref "R23") (pin "2") (pinfunction "2_2") (pintype "passive"))
      (node (ref "R29") (pin "2") (pinfunction "2_2") (pintype "passive"))
      (node (ref "R35") (pin "2") (pinfunction "2_2") (pintype "passive"))
      (node (ref "R45") (pin "2") (pinfunction "2_2") (pintype "passive"))
      (node (ref "R47") (pin "2") (pinfunction "2_2") (pintype "passive"))
      (node (ref "R5") (pin "2") (pinfunction "2_2") (pintype "passive"))
      (node (ref "R53") (pin "2") (pinfunction "2_2") (pintype "passive"))
      (node (ref "R59") (pin "2") (pinfunction "2_2") (pintype "passive"))
      (node (ref "R65") (pin "2") (pinfunction "2_2") (pintype "passive"))
      (node (ref "R71") (pin "2") (pinfunction "2_2") (pintype "passive"))
      (node (ref "R77") (pin "2") (pinfunction "2_2") (pintype "passive"))
      (node (ref "R83") (pin "2") (pinfunction "2_2") (pintype "passive"))
      (node (ref "R89") (pin "2") (pinfunction "2_2") (pintype "passive"))
      (node (ref "R95") (pin "2") (pinfunction "2_2") (pintype "passive"))
    )
    (net (code "99") (name "unconnected-(IC1A-+IN-Pad3)") (class "Default")
      (node (ref "IC1") (pin "3") (pinfunction "+IN_3") (pintype "input"))
    )
    (net (code "100") (name "unconnected-(IC2A-+IN-Pad3)") (class "Default")
      (node (ref "IC2") (pin "3") (pinfunction "+IN_3") (pintype "input"))
    )
    (net (code "101") (name "unconnected-(IC3A-+IN-Pad3)") (class "Default")
      (node (ref "IC3") (pin "3") (pinfunction "+IN_3") (pintype "input"))
    )
    (net (code "102") (name "unconnected-(IC4A-+IN-Pad3)") (class "Default")
      (node (ref "IC4") (pin "3") (pinfunction "+IN_3") (pintype "input"))
    )
    (net (code "103") (name "unconnected-(IC5A-+IN-Pad3)") (class "Default")
      (node (ref "IC5") (pin "3") (pinfunction "+IN_3") (pintype "input"))
    )
    (net (code "104") (name "unconnected-(IC6A-+IN-Pad3)") (class "Default")
      (node (ref "IC6") (pin "3") (pinfunction "+IN_3") (pintype "input"))
    )
    (net (code "105") (name "unconnected-(IC7A-+IN-Pad3)") (class "Default")
      (node (ref "IC7") (pin "3") (pinfunction "+IN_3") (pintype "input"))
    )
    (net (code "106") (name "unconnected-(IC8A-+IN-Pad3)") (class "Default")
      (node (ref "IC8") (pin "3") (pinfunction "+IN_3") (pintype "input"))
    )
    (net (code "107") (name "unconnected-(IC9A-+IN-Pad3)") (class "Default")
      (node (ref "IC9") (pin "3") (pinfunction "+IN_3") (pintype "input"))
    )
    (net (code "108") (name "unconnected-(IC10A-+IN-Pad3)") (class "Default")
      (node (ref "IC10") (pin "3") (pinfunction "+IN_3") (pintype "input"))
    )
    (net (code "109") (name "unconnected-(IC11A-+IN-Pad3)") (class "Default")
      (node (ref "IC11") (pin "3") (pinfunction "+IN_3") (pintype "input"))
    )
    (net (code "110") (name "unconnected-(IC12A-+IN-Pad3)") (class "Default")
      (node (ref "IC12") (pin "3") (pinfunction "+IN_3") (pintype "input"))
    )
    (net (code "111") (name "unconnected-(IC13A-+IN-Pad3)") (class "Default")
      (node (ref "IC13") (pin "3") (pinfunction "+IN_3") (pintype "input"))
    )
    (net (code "112") (name "unconnected-(IC14A-+IN-Pad3)") (class "Default")
      (node (ref "IC14") (pin "3") (pinfunction "+IN_3") (pintype "input"))
    )
    (net (code "113") (name "unconnected-(IC15A-+IN-Pad3)") (class "Default")
      (node (ref "IC15") (pin "3") (pinfunction "+IN_3") (pintype "input"))
    )
    (net (code "114") (name "unconnected-(IC16A-+IN-Pad3)") (class "Default")
      (node (ref "IC16") (pin "3") (pinfunction "+IN_3") (pintype "input"))
    )
  )
)
